# ALU.net
KiCad netlist of a schematic drawn in EAGLE
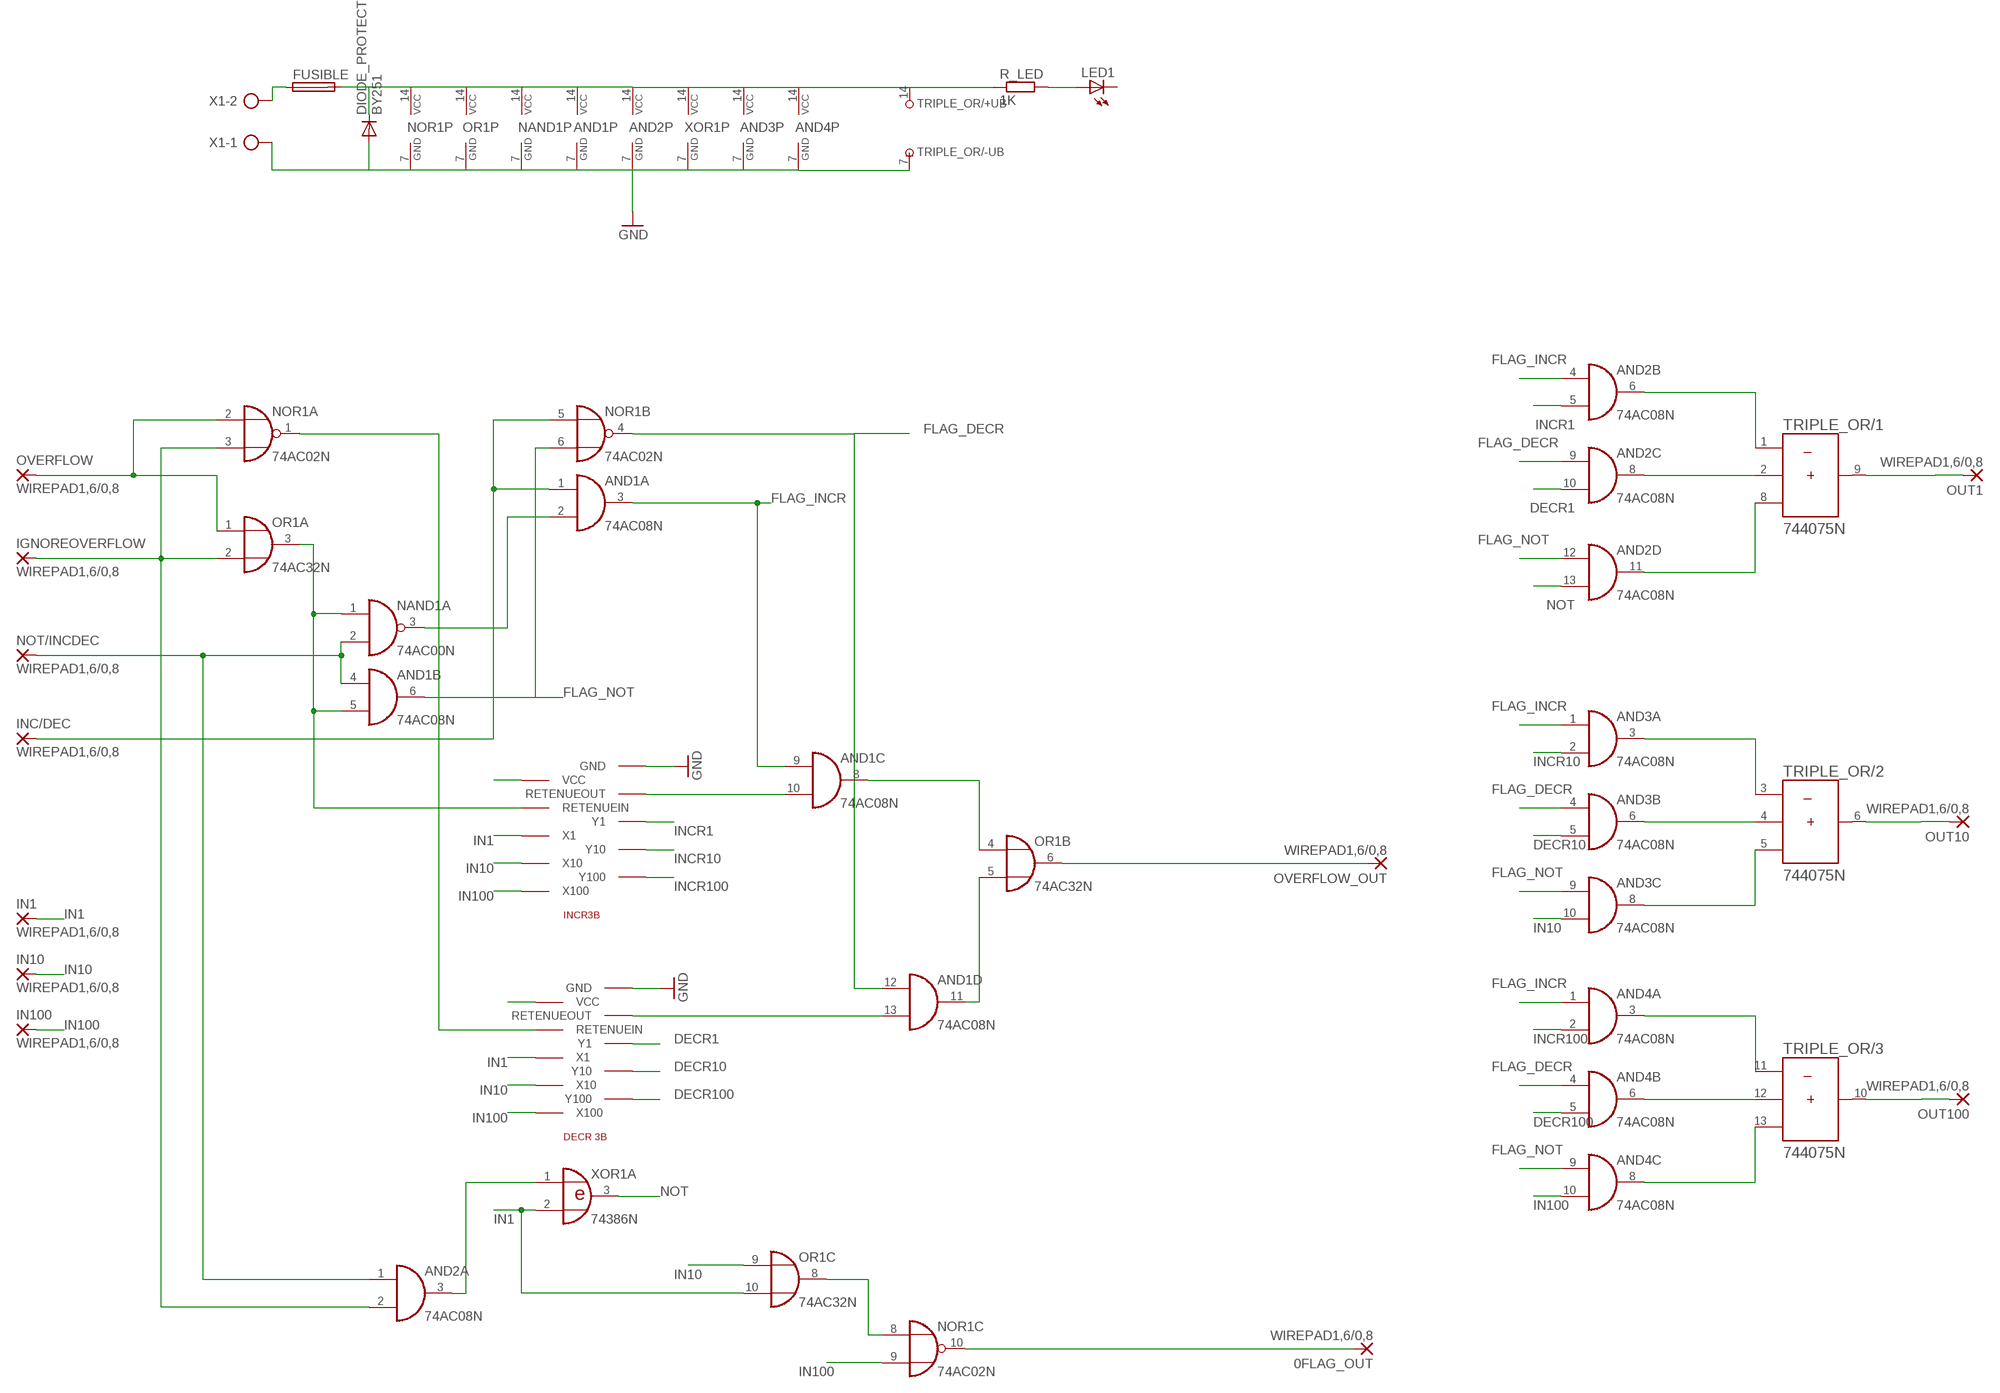
[diagram p0: schematic, sheet 1]

(export (version "E")
  (design (tool "Eeschema 10.0.6"))
  (components
    (comp (ref "0FLAG_OUT")
      (value "WIREPAD1,6/0,8")
      (footprint "eagle-import:1,6_0,8")
      (libsource (lib "eagle-import") (part "WIREPAD1,6/0,8"))
    )
    (comp (ref "AND1")
      (value "74AC08N")
      (footprint "eagle-import:DIL14")
      (libsource (lib "eagle-import") (part "7408NAC"))
    )
    (comp (ref "AND2")
      (value "74AC08N")
      (footprint "eagle-import:DIL14")
      (libsource (lib "eagle-import") (part "7408NAC"))
    )
    (comp (ref "AND3")
      (value "74AC08N")
      (footprint "eagle-import:DIL14")
      (libsource (lib "eagle-import") (part "7408NAC"))
    )
    (comp (ref "AND4")
      (value "74AC08N")
      (footprint "eagle-import:DIL14")
      (libsource (lib "eagle-import") (part "7408NAC"))
    )
    (comp (ref "DECR3B")
      (value "DECR3B")
      (footprint "eagle-import:DECR3B")
      (libsource (lib "eagle-import") (part "DECR3B"))
    )
    (comp (ref "DIODE_PROTECT")
      (value "BY251")
      (footprint "eagle-import:DO201-15")
      (libsource (lib "eagle-import") (part "BY251"))
    )
    (comp (ref "FUSIBLE")
      (value "SH22,5A")
      (footprint "eagle-import:SH22,5A")
      (fields (field (name "MPN") "0031.7701.11"))
      (libsource (lib "eagle-import") (part "SH22,5A"))
    )
    (comp (ref "IGNOREOVERFLOW")
      (value "WIREPAD1,6/0,8")
      (footprint "eagle-import:1,6_0,8")
      (libsource (lib "eagle-import") (part "WIREPAD1,6/0,8"))
    )
    (comp (ref "IN1")
      (value "WIREPAD1,6/0,8")
      (footprint "eagle-import:1,6_0,8")
      (libsource (lib "eagle-import") (part "WIREPAD1,6/0,8"))
    )
    (comp (ref "IN10")
      (value "WIREPAD1,6/0,8")
      (footprint "eagle-import:1,6_0,8")
      (libsource (lib "eagle-import") (part "WIREPAD1,6/0,8"))
    )
    (comp (ref "IN100")
      (value "WIREPAD1,6/0,8")
      (footprint "eagle-import:1,6_0,8")
      (libsource (lib "eagle-import") (part "WIREPAD1,6/0,8"))
    )
    (comp (ref "INC/DEC")
      (value "WIREPAD1,6/0,8")
      (footprint "eagle-import:1,6_0,8")
      (libsource (lib "eagle-import") (part "WIREPAD1,6/0,8"))
    )
    (comp (ref "INCR3B")
      (value "INCR3B")
      (footprint "eagle-import:INCR3B")
      (libsource (lib "eagle-import") (part "INCR3B"))
    )
    (comp (ref "LED1")
      (value "LEDSFH482")
      (footprint "eagle-import:SFH482")
      (libsource (lib "eagle-import") (part "LEDSFH482"))
    )
    (comp (ref "NAND1")
      (value "74AC00N")
      (footprint "eagle-import:DIL14")
      (libsource (lib "eagle-import") (part "7400NAC"))
    )
    (comp (ref "NOR1")
      (value "74AC02N")
      (footprint "eagle-import:DIL14")
      (libsource (lib "eagle-import") (part "7402NAC"))
    )
    (comp (ref "NOT/INCDEC")
      (value "WIREPAD1,6/0,8")
      (footprint "eagle-import:1,6_0,8")
      (libsource (lib "eagle-import") (part "WIREPAD1,6/0,8"))
    )
    (comp (ref "OR1")
      (value "74AC32N")
      (footprint "eagle-import:DIL14")
      (libsource (lib "eagle-import") (part "7432NAC"))
    )
    (comp (ref "OUT1")
      (value "WIREPAD1,6/0,8")
      (footprint "eagle-import:1,6_0,8")
      (libsource (lib "eagle-import") (part "WIREPAD1,6/0,8"))
    )
    (comp (ref "OUT10")
      (value "WIREPAD1,6/0,8")
      (footprint "eagle-import:1,6_0,8")
      (libsource (lib "eagle-import") (part "WIREPAD1,6/0,8"))
    )
    (comp (ref "OUT100")
      (value "WIREPAD1,6/0,8")
      (footprint "eagle-import:1,6_0,8")
      (libsource (lib "eagle-import") (part "WIREPAD1,6/0,8"))
    )
    (comp (ref "OVERFLOW")
      (value "WIREPAD1,6/0,8")
      (footprint "eagle-import:1,6_0,8")
      (libsource (lib "eagle-import") (part "WIREPAD1,6/0,8"))
    )
    (comp (ref "OVERFLOW_OUT")
      (value "WIREPAD1,6/0,8")
      (footprint "eagle-import:1,6_0,8")
      (libsource (lib "eagle-import") (part "WIREPAD1,6/0,8"))
    )
    (comp (ref "R_LED")
      (value "1K")
      (footprint "eagle-import:0207_10")
      (libsource (lib "eagle-import") (part "R-EU_0207/10"))
    )
    (comp (ref "TRIPLE_OR")
      (value "744075N")
      (footprint "eagle-import:DIL14")
      (libsource (lib "eagle-import") (part "744075N"))
    )
    (comp (ref "X1")
      (value "AK300/2")
      (footprint "eagle-import:AK300_2")
      (libsource (lib "eagle-import") (part "AK300/2"))
    )
    (comp (ref "XOR1")
      (value "74386N")
      (footprint "eagle-import:DIL14")
      (libsource (lib "eagle-import") (part "74386N"))
    )
  )
  (nets
    (net (code "1") (name "/DECR1") (class "Default")
      (node (ref "AND2") (pin "10") (pinfunction "I1_10") (pintype "input"))
      (node (ref "DECR3B") (pin "Y1") (pinfunction "Y1_Y1") (pintype "bidirectional"))
    )
    (net (code "2") (name "/DECR10") (class "Default")
      (node (ref "AND3") (pin "5") (pinfunction "I1_5") (pintype "input"))
      (node (ref "DECR3B") (pin "Y10") (pinfunction "Y10_Y10") (pintype "bidirectional"))
    )
    (net (code "3") (name "/DECR100") (class "Default")
      (node (ref "AND4") (pin "5") (pinfunction "I1_5") (pintype "input"))
      (node (ref "DECR3B") (pin "Y100") (pinfunction "Y100_Y100") (pintype "bidirectional"))
    )
    (net (code "4") (name "/FLAG_DECR") (class "Default")
      (node (ref "AND1") (pin "12") (pinfunction "I0_12") (pintype "input"))
      (node (ref "AND2") (pin "9") (pinfunction "I0_9") (pintype "input"))
      (node (ref "AND3") (pin "4") (pinfunction "I0_4") (pintype "input"))
      (node (ref "AND4") (pin "4") (pinfunction "I0_4") (pintype "input"))
      (node (ref "NOR1") (pin "4") (pinfunction "O_4") (pintype "output"))
    )
    (net (code "5") (name "/FLAG_INCR") (class "Default")
      (node (ref "AND1") (pin "3") (pinfunction "O_3") (pintype "output"))
      (node (ref "AND1") (pin "9") (pinfunction "I0_9") (pintype "input"))
      (node (ref "AND2") (pin "4") (pinfunction "I0_4") (pintype "input"))
      (node (ref "AND3") (pin "1") (pinfunction "I0_1") (pintype "input"))
      (node (ref "AND4") (pin "1") (pinfunction "I0_1") (pintype "input"))
    )
    (net (code "6") (name "/FLAG_NOT") (class "Default")
      (node (ref "AND1") (pin "6") (pinfunction "O_6") (pintype "output"))
      (node (ref "AND2") (pin "12") (pinfunction "I0_12") (pintype "input"))
      (node (ref "AND3") (pin "9") (pinfunction "I0_9") (pintype "input"))
      (node (ref "AND4") (pin "9") (pinfunction "I0_9") (pintype "input"))
      (node (ref "NOR1") (pin "6") (pinfunction "I1_6") (pintype "input"))
    )
    (net (code "7") (name "/IN1") (class "Default")
      (node (ref "DECR3B") (pin "X1") (pinfunction "X1_X1") (pintype "bidirectional"))
      (node (ref "IN1") (pin "1") (pinfunction "P_1") (pintype "passive"))
      (node (ref "INCR3B") (pin "X1") (pinfunction "X1_X1") (pintype "bidirectional"))
      (node (ref "OR1") (pin "10") (pinfunction "I1_10") (pintype "input"))
      (node (ref "XOR1") (pin "2") (pinfunction "I1_2") (pintype "input"))
    )
    (net (code "8") (name "/IN10") (class "Default")
      (node (ref "AND3") (pin "10") (pinfunction "I1_10") (pintype "input"))
      (node (ref "DECR3B") (pin "X10") (pinfunction "X10_X10") (pintype "bidirectional"))
      (node (ref "IN10") (pin "1") (pinfunction "P_1") (pintype "passive"))
      (node (ref "INCR3B") (pin "X10") (pinfunction "X10_X10") (pintype "bidirectional"))
      (node (ref "OR1") (pin "9") (pinfunction "I0_9") (pintype "input"))
    )
    (net (code "9") (name "/IN100") (class "Default")
      (node (ref "AND4") (pin "10") (pinfunction "I1_10") (pintype "input"))
      (node (ref "DECR3B") (pin "X100") (pinfunction "X100_X100") (pintype "bidirectional"))
      (node (ref "IN100") (pin "1") (pinfunction "P_1") (pintype "passive"))
      (node (ref "INCR3B") (pin "X100") (pinfunction "X100_X100") (pintype "bidirectional"))
      (node (ref "NOR1") (pin "9") (pinfunction "I1_9") (pintype "input"))
    )
    (net (code "10") (name "/INCR1") (class "Default")
      (node (ref "AND2") (pin "5") (pinfunction "I1_5") (pintype "input"))
      (node (ref "INCR3B") (pin "Y1") (pinfunction "Y1_Y1") (pintype "bidirectional"))
    )
    (net (code "11") (name "/INCR10") (class "Default")
      (node (ref "AND3") (pin "2") (pinfunction "I1_2") (pintype "input"))
      (node (ref "INCR3B") (pin "Y10") (pinfunction "Y10_Y10") (pintype "bidirectional"))
    )
    (net (code "12") (name "/INCR100") (class "Default")
      (node (ref "AND4") (pin "2") (pinfunction "I1_2") (pintype "input"))
      (node (ref "INCR3B") (pin "Y100") (pinfunction "Y100_Y100") (pintype "bidirectional"))
    )
    (net (code "13") (name "/NOT") (class "Default")
      (node (ref "AND2") (pin "13") (pinfunction "I1_13") (pintype "input"))
      (node (ref "XOR1") (pin "3") (pinfunction "O_3") (pintype "output"))
    )
    (net (code "14") (name "/OUT1") (class "Default")
      (node (ref "OUT1") (pin "1") (pinfunction "P_1") (pintype "passive"))
      (node (ref "TRIPLE_OR") (pin "9") (pinfunction "Y_9") (pintype "output"))
    )
    (net (code "15") (name "/OUT10") (class "Default")
      (node (ref "OUT10") (pin "1") (pinfunction "P_1") (pintype "passive"))
      (node (ref "TRIPLE_OR") (pin "6") (pinfunction "Y_6") (pintype "output"))
    )
    (net (code "16") (name "/OUT100") (class "Default")
      (node (ref "OUT100") (pin "1") (pinfunction "P_1") (pintype "passive"))
      (node (ref "TRIPLE_OR") (pin "10") (pinfunction "Y_10") (pintype "output"))
    )
    (net (code "17") (name "/VCC") (class "Default")
      (node (ref "AND1") (pin "14") (pinfunction "VCC_14") (pintype "power_in"))
      (node (ref "AND2") (pin "14") (pinfunction "VCC_14") (pintype "power_in"))
      (node (ref "AND3") (pin "14") (pinfunction "VCC_14") (pintype "power_in"))
      (node (ref "AND4") (pin "14") (pinfunction "VCC_14") (pintype "power_in"))
      (node (ref "DECR3B") (pin "VCC") (pinfunction "VCC_VCC") (pintype "bidirectional"))
      (node (ref "DIODE_PROTECT") (pin "C") (pinfunction "C_C") (pintype "passive"))
      (node (ref "FUSIBLE") (pin "2") (pinfunction "2_2") (pintype "passive"))
      (node (ref "INCR3B") (pin "VCC") (pinfunction "VCC_VCC") (pintype "bidirectional"))
      (node (ref "NAND1") (pin "14") (pinfunction "VCC_14") (pintype "power_in"))
      (node (ref "NOR1") (pin "14") (pinfunction "VCC_14") (pintype "power_in"))
      (node (ref "OR1") (pin "14") (pinfunction "VCC_14") (pintype "power_in"))
      (node (ref "R_LED") (pin "1") (pinfunction "1_1") (pintype "passive"))
      (node (ref "TRIPLE_OR") (pin "14") (pinfunction "+UB_14") (pintype "power_in"))
      (node (ref "XOR1") (pin "14") (pinfunction "VCC_14") (pintype "power_in"))
    )
    (net (code "18") (name "GND") (class "Default")
      (node (ref "AND1") (pin "7") (pinfunction "GND_7") (pintype "power_in"))
      (node (ref "AND2") (pin "7") (pinfunction "GND_7") (pintype "power_in"))
      (node (ref "AND3") (pin "7") (pinfunction "GND_7") (pintype "power_in"))
      (node (ref "AND4") (pin "7") (pinfunction "GND_7") (pintype "power_in"))
      (node (ref "DECR3B") (pin "GND") (pinfunction "GND_GND") (pintype "bidirectional"))
      (node (ref "DIODE_PROTECT") (pin "A") (pinfunction "A_A") (pintype "passive"))
      (node (ref "INCR3B") (pin "GND") (pinfunction "GND_GND") (pintype "bidirectional"))
      (node (ref "NAND1") (pin "7") (pinfunction "GND_7") (pintype "power_in"))
      (node (ref "NOR1") (pin "7") (pinfunction "GND_7") (pintype "power_in"))
      (node (ref "OR1") (pin "7") (pinfunction "GND_7") (pintype "power_in"))
      (node (ref "TRIPLE_OR") (pin "7") (pinfunction "-UB_7") (pintype "power_in"))
      (node (ref "X1") (pin "1") (pinfunction "KL_1") (pintype "passive"))
      (node (ref "XOR1") (pin "7") (pinfunction "GND_7") (pintype "power_in"))
    )
    (net (code "19") (name "Net-(0FLAG_OUT-P)") (class "Default")
      (node (ref "0FLAG_OUT") (pin "1") (pinfunction "P_1") (pintype "passive"))
      (node (ref "NOR1") (pin "10") (pinfunction "O_10") (pintype "output"))
    )
    (net (code "20") (name "Net-(AND1A-I0)") (class "Default")
      (node (ref "AND1") (pin "1") (pinfunction "I0_1") (pintype "input"))
      (node (ref "INC/DEC") (pin "1") (pinfunction "P_1") (pintype "passive"))
      (node (ref "NOR1") (pin "5") (pinfunction "I0_5") (pintype "input"))
    )
    (net (code "21") (name "Net-(AND1A-I1)") (class "Default")
      (node (ref "AND1") (pin "2") (pinfunction "I1_2") (pintype "input"))
      (node (ref "NAND1") (pin "3") (pinfunction "O_3") (pintype "output"))
    )
    (net (code "22") (name "Net-(AND1B-I0)") (class "Default")
      (node (ref "AND1") (pin "4") (pinfunction "I0_4") (pintype "input"))
      (node (ref "AND2") (pin "1") (pinfunction "I0_1") (pintype "input"))
      (node (ref "NAND1") (pin "2") (pinfunction "I1_2") (pintype "input"))
      (node (ref "NOT/INCDEC") (pin "1") (pinfunction "P_1") (pintype "passive"))
    )
    (net (code "23") (name "Net-(AND1B-I1)") (class "Default")
      (node (ref "AND1") (pin "5") (pinfunction "I1_5") (pintype "input"))
      (node (ref "INCR3B") (pin "RETENUEIN") (pinfunction "RETENUEIN_RETENUEIN") (pintype "bidirectional"))
      (node (ref "NAND1") (pin "1") (pinfunction "I0_1") (pintype "input"))
      (node (ref "OR1") (pin "3") (pinfunction "O_3") (pintype "output"))
    )
    (net (code "24") (name "Net-(AND1C-I1)") (class "Default")
      (node (ref "AND1") (pin "10") (pinfunction "I1_10") (pintype "input"))
      (node (ref "INCR3B") (pin "RETENUEOUT") (pinfunction "RETENUEOUT_RETENUEOUT") (pintype "bidirectional"))
    )
    (net (code "25") (name "Net-(AND1C-O)") (class "Default")
      (node (ref "AND1") (pin "8") (pinfunction "O_8") (pintype "output"))
      (node (ref "OR1") (pin "4") (pinfunction "I0_4") (pintype "input"))
    )
    (net (code "26") (name "Net-(AND1D-I1)") (class "Default")
      (node (ref "AND1") (pin "13") (pinfunction "I1_13") (pintype "input"))
      (node (ref "DECR3B") (pin "RETENUEOUT") (pinfunction "RETENUEOUT_RETENUEOUT") (pintype "bidirectional"))
    )
    (net (code "27") (name "Net-(AND1D-O)") (class "Default")
      (node (ref "AND1") (pin "11") (pinfunction "O_11") (pintype "output"))
      (node (ref "OR1") (pin "5") (pinfunction "I1_5") (pintype "input"))
    )
    (net (code "28") (name "Net-(AND2A-I1)") (class "Default")
      (node (ref "AND2") (pin "2") (pinfunction "I1_2") (pintype "input"))
      (node (ref "IGNOREOVERFLOW") (pin "1") (pinfunction "P_1") (pintype "passive"))
      (node (ref "NOR1") (pin "3") (pinfunction "I1_3") (pintype "input"))
      (node (ref "OR1") (pin "2") (pinfunction "I1_2") (pintype "input"))
    )
    (net (code "29") (name "Net-(AND2A-O)") (class "Default")
      (node (ref "AND2") (pin "3") (pinfunction "O_3") (pintype "output"))
      (node (ref "XOR1") (pin "1") (pinfunction "I0_1") (pintype "input"))
    )
    (net (code "30") (name "Net-(AND2B-O)") (class "Default")
      (node (ref "AND2") (pin "6") (pinfunction "O_6") (pintype "output"))
      (node (ref "TRIPLE_OR") (pin "1") (pinfunction "A_1") (pintype "input"))
    )
    (net (code "31") (name "Net-(AND2C-O)") (class "Default")
      (node (ref "AND2") (pin "8") (pinfunction "O_8") (pintype "output"))
      (node (ref "TRIPLE_OR") (pin "2") (pinfunction "B_2") (pintype "input"))
    )
    (net (code "32") (name "Net-(AND2D-O)") (class "Default")
      (node (ref "AND2") (pin "11") (pinfunction "O_11") (pintype "output"))
      (node (ref "TRIPLE_OR") (pin "8") (pinfunction "C_8") (pintype "input"))
    )
    (net (code "33") (name "Net-(AND3A-O)") (class "Default")
      (node (ref "AND3") (pin "3") (pinfunction "O_3") (pintype "output"))
      (node (ref "TRIPLE_OR") (pin "3") (pinfunction "A_3") (pintype "input"))
    )
    (net (code "34") (name "Net-(AND3B-O)") (class "Default")
      (node (ref "AND3") (pin "6") (pinfunction "O_6") (pintype "output"))
      (node (ref "TRIPLE_OR") (pin "4") (pinfunction "B_4") (pintype "input"))
    )
    (net (code "35") (name "Net-(AND3C-O)") (class "Default")
      (node (ref "AND3") (pin "8") (pinfunction "O_8") (pintype "output"))
      (node (ref "TRIPLE_OR") (pin "5") (pinfunction "C_5") (pintype "input"))
    )
    (net (code "36") (name "Net-(AND4A-O)") (class "Default")
      (node (ref "AND4") (pin "3") (pinfunction "O_3") (pintype "output"))
      (node (ref "TRIPLE_OR") (pin "11") (pinfunction "A_11") (pintype "input"))
    )
    (net (code "37") (name "Net-(AND4B-O)") (class "Default")
      (node (ref "AND4") (pin "6") (pinfunction "O_6") (pintype "output"))
      (node (ref "TRIPLE_OR") (pin "12") (pinfunction "B_12") (pintype "input"))
    )
    (net (code "38") (name "Net-(AND4C-O)") (class "Default")
      (node (ref "AND4") (pin "8") (pinfunction "O_8") (pintype "output"))
      (node (ref "TRIPLE_OR") (pin "13") (pinfunction "C_13") (pintype "input"))
    )
    (net (code "39") (name "Net-(LED1-PadA)") (class "Default")
      (node (ref "LED1") (pin "A") (pinfunction "A_A") (pintype "passive"))
      (node (ref "R_LED") (pin "2") (pinfunction "2_2") (pintype "passive"))
    )
    (net (code "40") (name "Net-(NOR1A-I0)") (class "Default")
      (node (ref "NOR1") (pin "2") (pinfunction "I0_2") (pintype "input"))
      (node (ref "OR1") (pin "1") (pinfunction "I0_1") (pintype "input"))
      (node (ref "OVERFLOW") (pin "1") (pinfunction "P_1") (pintype "passive"))
    )
    (net (code "41") (name "Net-(NOR1A-O)") (class "Default")
      (node (ref "DECR3B") (pin "RETENUEIN") (pinfunction "RETENUEIN_RETENUEIN") (pintype "bidirectional"))
      (node (ref "NOR1") (pin "1") (pinfunction "O_1") (pintype "output"))
    )
    (net (code "42") (name "Net-(NOR1C-I0)") (class "Default")
      (node (ref "NOR1") (pin "8") (pinfunction "I0_8") (pintype "input"))
      (node (ref "OR1") (pin "8") (pinfunction "O_8") (pintype "output"))
    )
    (net (code "43") (name "Net-(OR1B-O)") (class "Default")
      (node (ref "OR1") (pin "6") (pinfunction "O_6") (pintype "output"))
      (node (ref "OVERFLOW_OUT") (pin "1") (pinfunction "P_1") (pintype "passive"))
    )
    (net (code "44") (name "Net-(X1B-KL)") (class "Default")
      (node (ref "FUSIBLE") (pin "1") (pinfunction "1_1") (pintype "passive"))
      (node (ref "X1") (pin "2") (pinfunction "KL_2") (pintype "passive"))
    )
    (net (code "45") (name "unconnected-(LED1-C-PadK)") (class "Default")
      (node (ref "LED1") (pin "K") (pinfunction "C_K") (pintype "passive"))
    )
  )
)
